# CommsTestBoardV2.net
KiCad netlist of a schematic drawn in EAGLE
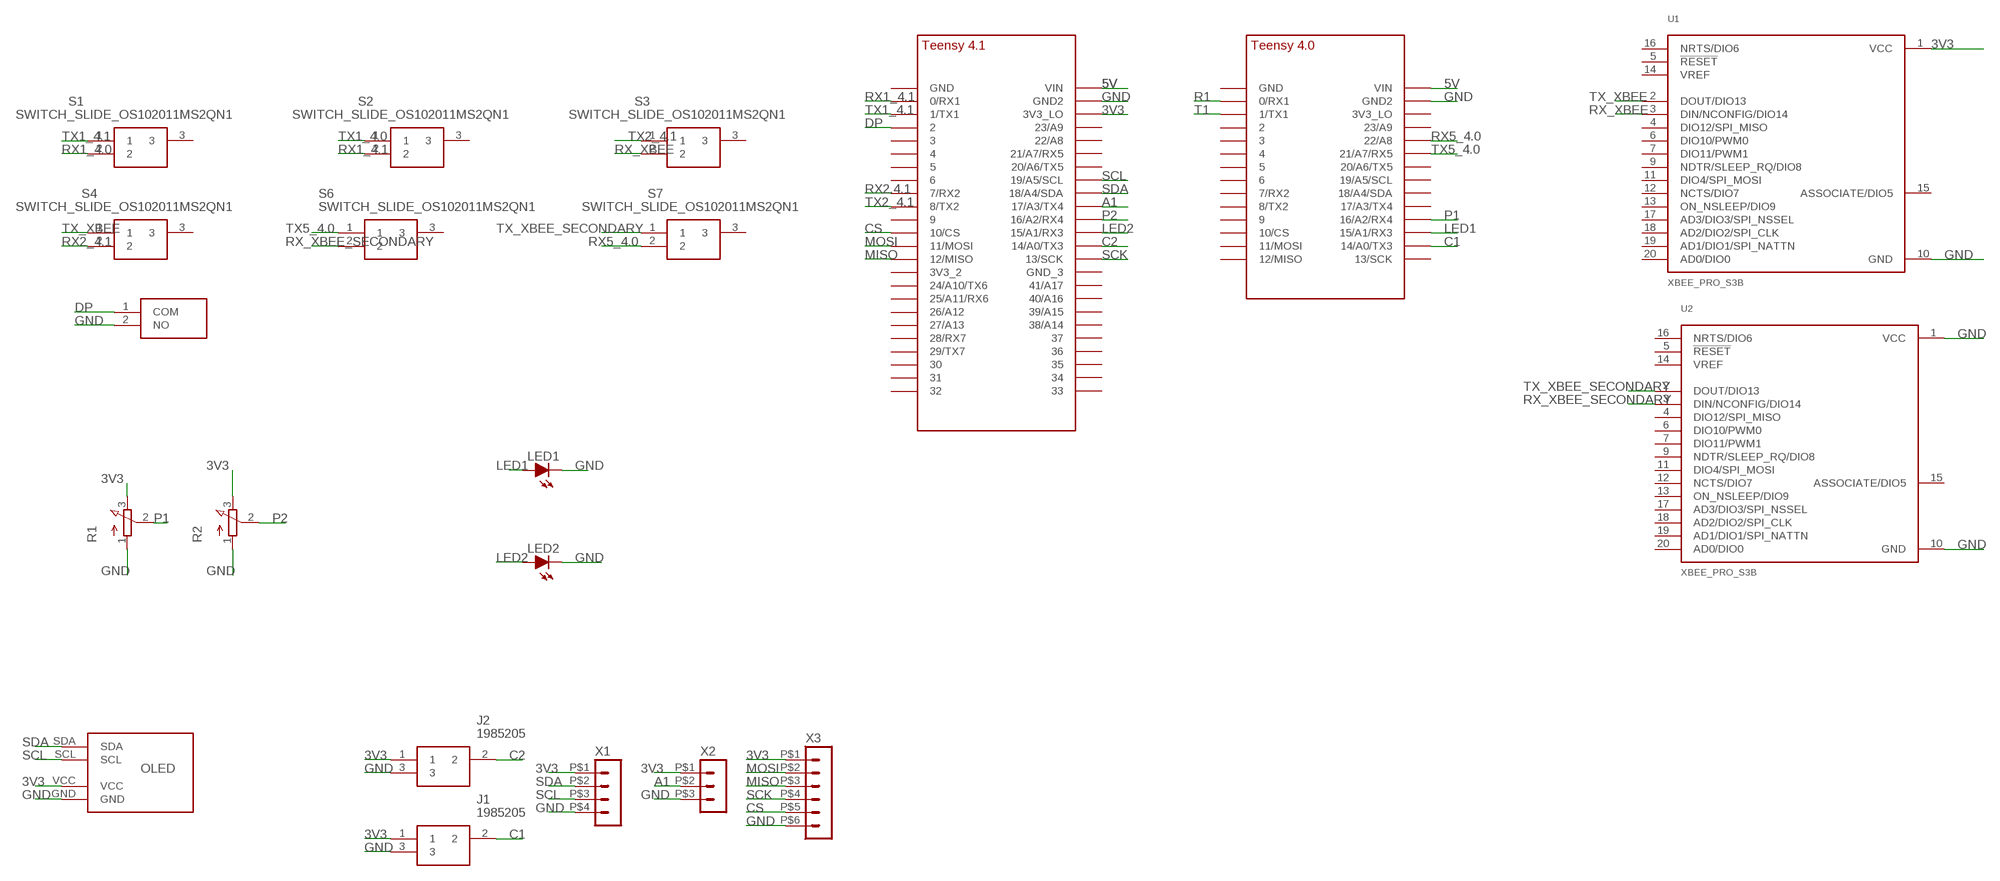
[diagram p0: schematic, sheet 1]

(export (version "E")
  (design (tool "Eeschema 10.0.6"))
  (components
    (comp (ref "J1")
      (value "1985205")
      (footprint "eagle-import:1985205")
      (fields (field (name "MOUSER_PART_NUMBER") "651-1985205"))
      (libsource (lib "eagle-import") (part "1985205"))
    )
    (comp (ref "J2")
      (value "1985205")
      (footprint "eagle-import:1985205")
      (fields (field (name "MOUSER_PART_NUMBER") "651-1985205"))
      (libsource (lib "eagle-import") (part "1985205"))
    )
    (comp (ref "LED1")
      (value "LED-5MM")
      (footprint "eagle-import:LED-5MM")
      (libsource (lib "eagle-import") (part "LED-5MM"))
    )
    (comp (ref "LED2")
      (value "LED-5MM")
      (footprint "eagle-import:LED-5MM")
      (libsource (lib "eagle-import") (part "LED-5MM"))
    )
    (comp (ref "R1")
      (value "POTENTIOMETER")
      (footprint "eagle-import:3RP_1610N")
      (libsource (lib "eagle-import") (part "POTENTIOMETER"))
    )
    (comp (ref "R2")
      (value "POTENTIOMETER")
      (footprint "eagle-import:3RP_1610N")
      (libsource (lib "eagle-import") (part "POTENTIOMETER"))
    )
    (comp (ref "S1")
      (value "SWITCH_SLIDE_OS102011MS2QN1")
      (footprint "eagle-import:OS102011MA1QN1")
      (fields
        (field (name "ARROW_PART_NUMBER") "OS102011MS2QN1")
        (field (name "MOUSER_PART_NUMBER") "611-OS102011MS2QN1")
      )
      (libsource (lib "eagle-import") (part "SWITCH_SLIDE_OS102011MS2QN1"))
    )
    (comp (ref "S2")
      (value "SWITCH_SLIDE_OS102011MS2QN1")
      (footprint "eagle-import:OS102011MA1QN1")
      (fields
        (field (name "ARROW_PART_NUMBER") "OS102011MS2QN1")
        (field (name "MOUSER_PART_NUMBER") "611-OS102011MS2QN1")
      )
      (libsource (lib "eagle-import") (part "SWITCH_SLIDE_OS102011MS2QN1"))
    )
    (comp (ref "S3")
      (value "SWITCH_SLIDE_OS102011MS2QN1")
      (footprint "eagle-import:OS102011MA1QN1")
      (fields
        (field (name "ARROW_PART_NUMBER") "OS102011MS2QN1")
        (field (name "MOUSER_PART_NUMBER") "611-OS102011MS2QN1")
      )
      (libsource (lib "eagle-import") (part "SWITCH_SLIDE_OS102011MS2QN1"))
    )
    (comp (ref "S4")
      (value "SWITCH_SLIDE_OS102011MS2QN1")
      (footprint "eagle-import:OS102011MA1QN1")
      (fields
        (field (name "ARROW_PART_NUMBER") "OS102011MS2QN1")
        (field (name "MOUSER_PART_NUMBER") "611-OS102011MS2QN1")
      )
      (libsource (lib "eagle-import") (part "SWITCH_SLIDE_OS102011MS2QN1"))
    )
    (comp (ref "S5")
      (value "PTS636_SL50_LFS")
      (footprint "eagle-import:PTS636SL50LFS")
      (fields
        (field (name "ARROW_PART_NUMBER") "PTS636 SL50 LFS")
        (field (name "MOUSER_PART_NUMBER") "611-PTS636SL50LFS")
      )
      (libsource (lib "eagle-import") (part "PTS636_SL50_LFS"))
    )
    (comp (ref "S6")
      (value "SWITCH_SLIDE_OS102011MS2QN1")
      (footprint "eagle-import:OS102011MA1QN1")
      (fields
        (field (name "ARROW_PART_NUMBER") "OS102011MS2QN1")
        (field (name "MOUSER_PART_NUMBER") "611-OS102011MS2QN1")
      )
      (libsource (lib "eagle-import") (part "SWITCH_SLIDE_OS102011MS2QN1"))
    )
    (comp (ref "S7")
      (value "SWITCH_SLIDE_OS102011MS2QN1")
      (footprint "eagle-import:OS102011MA1QN1")
      (fields
        (field (name "ARROW_PART_NUMBER") "OS102011MS2QN1")
        (field (name "MOUSER_PART_NUMBER") "611-OS102011MS2QN1")
      )
      (libsource (lib "eagle-import") (part "SWITCH_SLIDE_OS102011MS2QN1"))
    )
    (comp (ref "U$1")
      (value "TEENSY_4.0_SIMPLE")
      (footprint "eagle-import:TEENSY_4.0_SIMPLE")
      (libsource (lib "eagle-import") (part "TEENSY_4.0_SIMPLE"))
    )
    (comp (ref "U$3")
      (value "TEENSY_4.1_SIMPLE")
      (footprint "eagle-import:TEENSY_4.1_SIMPLE")
      (libsource (lib "eagle-import") (part "TEENSY_4.1_SIMPLE"))
    )
    (comp (ref "U$4")
      (value "OLED_SSD1306")
      (footprint "eagle-import:OLED_SSD1306")
      (libsource (lib "eagle-import") (part "OLED_SSD1306"))
    )
    (comp (ref "U1")
      (value "XBEE_PRO_S3B")
      (footprint "eagle-import:XBEE_PRO_S3B")
      (fields
        (field (name "DIGI-KEY_PART_NUMBER") "602-1293-ND")
        (field (name "MF") "Digi International")
        (field (name "MP") "XBP9B-XCST-001")
      )
      (libsource (lib "eagle-import") (part "XBEE_PRO_S3B"))
    )
    (comp (ref "U2")
      (value "XBEE_PRO_S3B")
      (footprint "eagle-import:XBEE_PRO_S3B")
      (fields
        (field (name "DIGI-KEY_PART_NUMBER") "602-1293-ND")
        (field (name "MF") "Digi International")
        (field (name "MP") "XBP9B-XCST-001")
      )
      (libsource (lib "eagle-import") (part "XBEE_PRO_S3B"))
    )
    (comp (ref "X1")
      (value "HEADER_POS4_43045-0401")
      (footprint "eagle-import:43045-0400")
      (libsource (lib "eagle-import") (part "HEADER_POS4_?43045-0401"))
    )
    (comp (ref "X2")
      (value "HEADER_POS3_43650-0300")
      (footprint "eagle-import:43650-0300")
      (libsource (lib "eagle-import") (part "HEADER_POS3_?43650-0300"))
    )
    (comp (ref "X3")
      (value "HEADER_POS6_43045-0600")
      (footprint "eagle-import:43045-0600")
      (libsource (lib "eagle-import") (part "HEADER_POS6_?43045-0600"))
    )
  )
  (nets
    (net (code "1") (name "/3V3") (class "Default")
      (node (ref "J1") (pin "1") (pinfunction "1_1") (pintype "bidirectional"))
      (node (ref "J2") (pin "1") (pinfunction "1_1") (pintype "bidirectional"))
      (node (ref "R1") (pin "3") (pinfunction "E_3") (pintype "passive"))
      (node (ref "R2") (pin "3") (pinfunction "E_3") (pintype "passive"))
      (node (ref "U$3") (pin "3V3_LO") (pinfunction "3V3_LO_3V3_LO") (pintype "bidirectional"))
      (node (ref "U$4") (pin "VCC") (pinfunction "VCC_VCC") (pintype "bidirectional"))
      (node (ref "U1") (pin "1") (pinfunction "VCC_1") (pintype "power_in"))
      (node (ref "X1") (pin "P$1") (pinfunction "1_P$1") (pintype "passive"))
      (node (ref "X2") (pin "P$1") (pinfunction "1_P$1") (pintype "passive"))
      (node (ref "X3") (pin "P$1") (pinfunction "1_P$1") (pintype "passive"))
    )
    (net (code "2") (name "/5V") (class "Default")
      (node (ref "U$1") (pin "VIN") (pinfunction "VIN_VIN") (pintype "bidirectional"))
      (node (ref "U$3") (pin "VIN") (pinfunction "VIN_VIN") (pintype "bidirectional"))
    )
    (net (code "3") (name "/A1") (class "Default")
      (node (ref "U$3") (pin "17/A3") (pinfunction "17/A3/TX4_17/A3") (pintype "bidirectional"))
      (node (ref "X2") (pin "P$2") (pinfunction "2_P$2") (pintype "passive"))
    )
    (net (code "4") (name "/C1") (class "Default")
      (node (ref "J1") (pin "2") (pinfunction "2_2") (pintype "bidirectional"))
      (node (ref "U$1") (pin "14/A0") (pinfunction "14/A0/TX3_14/A0") (pintype "bidirectional"))
    )
    (net (code "5") (name "/C2") (class "Default")
      (node (ref "J2") (pin "2") (pinfunction "2_2") (pintype "bidirectional"))
      (node (ref "U$3") (pin "14/A0") (pinfunction "14/A0/TX3_14/A0") (pintype "bidirectional"))
    )
    (net (code "6") (name "/CS") (class "Default")
      (node (ref "U$3") (pin "10/CS") (pinfunction "10/CS_10/CS") (pintype "bidirectional"))
      (node (ref "X3") (pin "P$5") (pinfunction "5_P$5") (pintype "passive"))
    )
    (net (code "7") (name "/DP") (class "Default")
      (node (ref "S5") (pin "1") (pinfunction "COM_1") (pintype "bidirectional"))
      (node (ref "U$3") (pin "2") (pinfunction "2_2") (pintype "bidirectional"))
    )
    (net (code "8") (name "/GND") (class "Default")
      (node (ref "J1") (pin "3") (pinfunction "3_3") (pintype "bidirectional"))
      (node (ref "J2") (pin "3") (pinfunction "3_3") (pintype "bidirectional"))
      (node (ref "LED1") (pin "K") (pinfunction "C_K") (pintype "passive"))
      (node (ref "LED2") (pin "K") (pinfunction "C_K") (pintype "passive"))
      (node (ref "R1") (pin "1") (pinfunction "A_1") (pintype "passive"))
      (node (ref "R2") (pin "1") (pinfunction "A_1") (pintype "passive"))
      (node (ref "S5") (pin "2") (pinfunction "NO_2") (pintype "bidirectional"))
      (node (ref "U$1") (pin "GND2") (pinfunction "GND2_GND2") (pintype "bidirectional"))
      (node (ref "U$3") (pin "GND2") (pinfunction "GND2_GND2") (pintype "bidirectional"))
      (node (ref "U$4") (pin "GND") (pinfunction "GND_GND") (pintype "bidirectional"))
      (node (ref "U1") (pin "10") (pinfunction "GND_10") (pintype "power_in"))
      (node (ref "U2") (pin "1") (pinfunction "VCC_1") (pintype "power_in"))
      (node (ref "U2") (pin "10") (pinfunction "GND_10") (pintype "power_in"))
      (node (ref "X1") (pin "P$4") (pinfunction "4_P$4") (pintype "passive"))
      (node (ref "X2") (pin "P$3") (pinfunction "3_P$3") (pintype "passive"))
      (node (ref "X3") (pin "P$6") (pinfunction "6_P$6") (pintype "passive"))
    )
    (net (code "9") (name "/LED1") (class "Default")
      (node (ref "LED1") (pin "A") (pinfunction "A_A") (pintype "passive"))
      (node (ref "U$1") (pin "15/A1") (pinfunction "15/A1/RX3_15/A1") (pintype "bidirectional"))
    )
    (net (code "10") (name "/LED2") (class "Default")
      (node (ref "LED2") (pin "A") (pinfunction "A_A") (pintype "passive"))
      (node (ref "U$3") (pin "15/A1") (pinfunction "15/A1/RX3_15/A1") (pintype "bidirectional"))
    )
    (net (code "11") (name "/MISO") (class "Default")
      (node (ref "U$3") (pin "12/MISO") (pinfunction "12/MISO_12/MISO") (pintype "bidirectional"))
      (node (ref "X3") (pin "P$3") (pinfunction "3_P$3") (pintype "passive"))
    )
    (net (code "12") (name "/MOSI") (class "Default")
      (node (ref "U$3") (pin "11/MOSI") (pinfunction "11/MOSI_11/MOSI") (pintype "bidirectional"))
      (node (ref "X3") (pin "P$2") (pinfunction "2_P$2") (pintype "passive"))
    )
    (net (code "13") (name "/P1") (class "Default")
      (node (ref "R1") (pin "2") (pinfunction "S_2") (pintype "passive"))
      (node (ref "U$1") (pin "16/A2") (pinfunction "16/A2/RX4_16/A2") (pintype "bidirectional"))
    )
    (net (code "14") (name "/P2") (class "Default")
      (node (ref "R2") (pin "2") (pinfunction "S_2") (pintype "passive"))
      (node (ref "U$3") (pin "16/A2") (pinfunction "16/A2/RX4_16/A2") (pintype "bidirectional"))
    )
    (net (code "15") (name "/R1") (class "Default")
      (node (ref "U$1") (pin "0/RX") (pinfunction "0/RX1_0/RX") (pintype "bidirectional"))
    )
    (net (code "16") (name "/RX1_4.0") (class "Default")
      (node (ref "S1") (pin "2") (pinfunction "2_2") (pintype "bidirectional"))
    )
    (net (code "17") (name "/RX1_4.1") (class "Default")
      (node (ref "S2") (pin "2") (pinfunction "2_2") (pintype "bidirectional"))
      (node (ref "U$3") (pin "0/RX") (pinfunction "0/RX1_0/RX") (pintype "bidirectional"))
    )
    (net (code "18") (name "/RX2.4.1") (class "Default")
      (node (ref "U$3") (pin "7") (pinfunction "7/RX2_7") (pintype "bidirectional"))
    )
    (net (code "19") (name "/RX2_4.1") (class "Default")
      (node (ref "S4") (pin "2") (pinfunction "2_2") (pintype "bidirectional"))
    )
    (net (code "20") (name "/RX5_4.0") (class "Default")
      (node (ref "S7") (pin "2") (pinfunction "2_2") (pintype "bidirectional"))
      (node (ref "U$1") (pin "22/A8") (pinfunction "22/A8_22/A8") (pintype "bidirectional"))
    )
    (net (code "21") (name "/RX_XBEE") (class "Default")
      (node (ref "S3") (pin "2") (pinfunction "2_2") (pintype "bidirectional"))
      (node (ref "U1") (pin "3") (pinfunction "DIN/NCONFIG/DIO14_3") (pintype "bidirectional"))
    )
    (net (code "22") (name "/RX_XBEE_SECONDARY") (class "Default")
      (node (ref "S6") (pin "2") (pinfunction "2_2") (pintype "bidirectional"))
      (node (ref "U2") (pin "3") (pinfunction "DIN/NCONFIG/DIO14_3") (pintype "bidirectional"))
    )
    (net (code "23") (name "/SCK") (class "Default")
      (node (ref "U$3") (pin "13/SCK") (pinfunction "13/SCK_13/SCK") (pintype "bidirectional"))
      (node (ref "X3") (pin "P$4") (pinfunction "4_P$4") (pintype "passive"))
    )
    (net (code "24") (name "/SCL") (class "Default")
      (node (ref "U$3") (pin "19/A5/SCL") (pinfunction "19/A5/SCL_19/A5/SCL") (pintype "bidirectional"))
      (node (ref "U$4") (pin "SCL") (pinfunction "SCL_SCL") (pintype "bidirectional"))
      (node (ref "X1") (pin "P$3") (pinfunction "3_P$3") (pintype "passive"))
    )
    (net (code "25") (name "/SDA") (class "Default")
      (node (ref "U$3") (pin "18/A4/SDA") (pinfunction "18/A4/SDA_18/A4/SDA") (pintype "bidirectional"))
      (node (ref "U$4") (pin "SDA") (pinfunction "SDA_SDA") (pintype "bidirectional"))
      (node (ref "X1") (pin "P$2") (pinfunction "2_P$2") (pintype "passive"))
    )
    (net (code "26") (name "/T1") (class "Default")
      (node (ref "U$1") (pin "1/TX") (pinfunction "1/TX1_1/TX") (pintype "bidirectional"))
    )
    (net (code "27") (name "/TX1_4.0") (class "Default")
      (node (ref "S2") (pin "1") (pinfunction "1_1") (pintype "bidirectional"))
    )
    (net (code "28") (name "/TX1_4.1") (class "Default")
      (node (ref "S1") (pin "1") (pinfunction "1_1") (pintype "bidirectional"))
      (node (ref "U$3") (pin "1/TX") (pinfunction "1/TX1_1/TX") (pintype "bidirectional"))
    )
    (net (code "29") (name "/TX2_4.1") (class "Default")
      (node (ref "S3") (pin "1") (pinfunction "1_1") (pintype "bidirectional"))
      (node (ref "U$3") (pin "8") (pinfunction "8/TX2_8") (pintype "bidirectional"))
    )
    (net (code "30") (name "/TX5_4.0") (class "Default")
      (node (ref "S6") (pin "1") (pinfunction "1_1") (pintype "bidirectional"))
      (node (ref "U$1") (pin "21/A7") (pinfunction "21/A7/RX5_21/A7") (pintype "bidirectional"))
    )
    (net (code "31") (name "/TX_XBEE") (class "Default")
      (node (ref "S4") (pin "1") (pinfunction "1_1") (pintype "bidirectional"))
      (node (ref "U1") (pin "2") (pinfunction "DOUT/DIO13_2") (pintype "bidirectional"))
    )
    (net (code "32") (name "/TX_XBEE_SECONDARY") (class "Default")
      (node (ref "S7") (pin "1") (pinfunction "1_1") (pintype "bidirectional"))
      (node (ref "U2") (pin "2") (pinfunction "DOUT/DIO13_2") (pintype "bidirectional"))
    )
    (net (code "33") (name "unconnected-(S1-Pad3)") (class "Default")
      (node (ref "S1") (pin "3") (pinfunction "3_3") (pintype "bidirectional"))
    )
    (net (code "34") (name "unconnected-(S2-Pad3)") (class "Default")
      (node (ref "S2") (pin "3") (pinfunction "3_3") (pintype "bidirectional"))
    )
    (net (code "35") (name "unconnected-(S3-Pad3)") (class "Default")
      (node (ref "S3") (pin "3") (pinfunction "3_3") (pintype "bidirectional"))
    )
    (net (code "36") (name "unconnected-(S4-Pad3)") (class "Default")
      (node (ref "S4") (pin "3") (pinfunction "3_3") (pintype "bidirectional"))
    )
    (net (code "37") (name "unconnected-(S6-Pad3)") (class "Default")
      (node (ref "S6") (pin "3") (pinfunction "3_3") (pintype "bidirectional"))
    )
    (net (code "38") (name "unconnected-(S7-Pad3)") (class "Default")
      (node (ref "S7") (pin "3") (pinfunction "3_3") (pintype "bidirectional"))
    )
    (net (code "39") (name "unconnected-(U$1-3-Pad3{slash}CANTX)") (class "Default")
      (node (ref "U$1") (pin "3/CANTX") (pinfunction "3_3/CANTX") (pintype "bidirectional"))
    )
    (net (code "40") (name "unconnected-(U$1-4-Pad4{slash}CANRX)") (class "Default")
      (node (ref "U$1") (pin "4/CANRX") (pinfunction "4_4/CANRX") (pintype "bidirectional"))
    )
    (net (code "41") (name "unconnected-(U$1-7{slash}RX2-Pad7)") (class "Default")
      (node (ref "U$1") (pin "7") (pinfunction "7/RX2_7") (pintype "bidirectional"))
    )
    (net (code "42") (name "unconnected-(U$1-8{slash}TX2-Pad8)") (class "Default")
      (node (ref "U$1") (pin "8") (pinfunction "8/TX2_8") (pintype "bidirectional"))
    )
    (net (code "43") (name "unconnected-(U$1-9-Pad9{slash}CS)") (class "Default")
      (node (ref "U$1") (pin "9/CS") (pinfunction "9_9/CS") (pintype "bidirectional"))
    )
    (net (code "44") (name "unconnected-(U$1-17{slash}A3{slash}TX4-Pad17{slash}A3)") (class "Default")
      (node (ref "U$1") (pin "17/A3") (pinfunction "17/A3/TX4_17/A3") (pintype "bidirectional"))
    )
    (net (code "45") (name "unconnected-(U$1-20{slash}A6{slash}TX5-Pad20{slash}A6)") (class "Default")
      (node (ref "U$1") (pin "20/A6") (pinfunction "20/A6/TX5_20/A6") (pintype "bidirectional"))
    )
    (net (code "46") (name "unconnected-(U$1-Pad2)") (class "Default")
      (node (ref "U$1") (pin "2") (pinfunction "2_2") (pintype "bidirectional"))
    )
    (net (code "47") (name "unconnected-(U$1-Pad3V3_LO)") (class "Default")
      (node (ref "U$1") (pin "3V3_LO") (pinfunction "3V3_LO_3V3_LO") (pintype "bidirectional"))
    )
    (net (code "48") (name "unconnected-(U$1-Pad5)") (class "Default")
      (node (ref "U$1") (pin "5") (pinfunction "5_5") (pintype "bidirectional"))
    )
    (net (code "49") (name "unconnected-(U$1-Pad6)") (class "Default")
      (node (ref "U$1") (pin "6") (pinfunction "6_6") (pintype "bidirectional"))
    )
    (net (code "50") (name "unconnected-(U$1-Pad10{slash}CS)") (class "Default")
      (node (ref "U$1") (pin "10/CS") (pinfunction "10/CS_10/CS") (pintype "bidirectional"))
    )
    (net (code "51") (name "unconnected-(U$1-Pad11{slash}MOSI)") (class "Default")
      (node (ref "U$1") (pin "11/MOSI") (pinfunction "11/MOSI_11/MOSI") (pintype "bidirectional"))
    )
    (net (code "52") (name "unconnected-(U$1-Pad12{slash}MISO)") (class "Default")
      (node (ref "U$1") (pin "12/MISO") (pinfunction "12/MISO_12/MISO") (pintype "bidirectional"))
    )
    (net (code "53") (name "unconnected-(U$1-Pad13{slash}SCK)") (class "Default")
      (node (ref "U$1") (pin "13/SCK") (pinfunction "13/SCK_13/SCK") (pintype "bidirectional"))
    )
    (net (code "54") (name "unconnected-(U$1-Pad18{slash}A4{slash}SDA)") (class "Default")
      (node (ref "U$1") (pin "18/A4/SDA") (pinfunction "18/A4/SDA_18/A4/SDA") (pintype "bidirectional"))
    )
    (net (code "55") (name "unconnected-(U$1-Pad19{slash}A5{slash}SCL)") (class "Default")
      (node (ref "U$1") (pin "19/A5/SCL") (pinfunction "19/A5/SCL_19/A5/SCL") (pintype "bidirectional"))
    )
    (net (code "56") (name "unconnected-(U$1-Pad23{slash}A9)") (class "Default")
      (node (ref "U$1") (pin "23/A9") (pinfunction "23/A9_23/A9") (pintype "bidirectional"))
    )
    (net (code "57") (name "unconnected-(U$1-PadGND)") (class "Default")
      (node (ref "U$1") (pin "GND") (pinfunction "GND_GND") (pintype "bidirectional"))
    )
    (net (code "58") (name "unconnected-(U$3-3-Pad3{slash}CANTX)") (class "Default")
      (node (ref "U$3") (pin "3/CANTX") (pinfunction "3_3/CANTX") (pintype "bidirectional"))
    )
    (net (code "59") (name "unconnected-(U$3-4-Pad4{slash}CANRX)") (class "Default")
      (node (ref "U$3") (pin "4/CANRX") (pinfunction "4_4/CANRX") (pintype "bidirectional"))
    )
    (net (code "60") (name "unconnected-(U$3-9-Pad9{slash}CS)") (class "Default")
      (node (ref "U$3") (pin "9/CS") (pinfunction "9_9/CS") (pintype "bidirectional"))
    )
    (net (code "61") (name "unconnected-(U$3-20{slash}A6{slash}TX5-Pad20{slash}A6)") (class "Default")
      (node (ref "U$3") (pin "20/A6") (pinfunction "20/A6/TX5_20/A6") (pintype "bidirectional"))
    )
    (net (code "62") (name "unconnected-(U$3-21{slash}A7{slash}RX5-Pad21{slash}A7)") (class "Default")
      (node (ref "U$3") (pin "21/A7") (pinfunction "21/A7/RX5_21/A7") (pintype "bidirectional"))
    )
    (net (code "63") (name "unconnected-(U$3-24{slash}A10{slash}TX6-Pad24{slash}A10)") (class "Default")
      (node (ref "U$3") (pin "24/A10") (pinfunction "24/A10/TX6_24/A10") (pintype "bidirectional"))
    )
    (net (code "64") (name "unconnected-(U$3-25{slash}A11{slash}RX6-Pad25{slash}A11)") (class "Default")
      (node (ref "U$3") (pin "25/A11") (pinfunction "25/A11/RX6_25/A11") (pintype "bidirectional"))
    )
    (net (code "65") (name "unconnected-(U$3-28{slash}RX7-Pad28)") (class "Default")
      (node (ref "U$3") (pin "28") (pinfunction "28/RX7_28") (pintype "bidirectional"))
    )
    (net (code "66") (name "unconnected-(U$3-29{slash}TX7-Pad29)") (class "Default")
      (node (ref "U$3") (pin "29") (pinfunction "29/TX7_29") (pintype "bidirectional"))
    )
    (net (code "67") (name "unconnected-(U$3-GND_3-PadGND3)") (class "Default")
      (node (ref "U$3") (pin "GND3") (pinfunction "GND_3_GND3") (pintype "bidirectional"))
    )
    (net (code "68") (name "unconnected-(U$3-Pad3V3_2)") (class "Default")
      (node (ref "U$3") (pin "3V3_2") (pinfunction "3V3_2_3V3_2") (pintype "bidirectional"))
    )
    (net (code "69") (name "unconnected-(U$3-Pad5)") (class "Default")
      (node (ref "U$3") (pin "5") (pinfunction "5_5") (pintype "bidirectional"))
    )
    (net (code "70") (name "unconnected-(U$3-Pad6)") (class "Default")
      (node (ref "U$3") (pin "6") (pinfunction "6_6") (pintype "bidirectional"))
    )
    (net (code "71") (name "unconnected-(U$3-Pad22{slash}A8)") (class "Default")
      (node (ref "U$3") (pin "22/A8") (pinfunction "22/A8_22/A8") (pintype "bidirectional"))
    )
    (net (code "72") (name "unconnected-(U$3-Pad23{slash}A9)") (class "Default")
      (node (ref "U$3") (pin "23/A9") (pinfunction "23/A9_23/A9") (pintype "bidirectional"))
    )
    (net (code "73") (name "unconnected-(U$3-Pad26{slash}A12)") (class "Default")
      (node (ref "U$3") (pin "26/A12") (pinfunction "26/A12_26/A12") (pintype "bidirectional"))
    )
    (net (code "74") (name "unconnected-(U$3-Pad27{slash}A13)") (class "Default")
      (node (ref "U$3") (pin "27/A13") (pinfunction "27/A13_27/A13") (pintype "bidirectional"))
    )
    (net (code "75") (name "unconnected-(U$3-Pad30)") (class "Default")
      (node (ref "U$3") (pin "30") (pinfunction "30_30") (pintype "bidirectional"))
    )
    (net (code "76") (name "unconnected-(U$3-Pad31)") (class "Default")
      (node (ref "U$3") (pin "31") (pinfunction "31_31") (pintype "bidirectional"))
    )
    (net (code "77") (name "unconnected-(U$3-Pad32)") (class "Default")
      (node (ref "U$3") (pin "32") (pinfunction "32_32") (pintype "bidirectional"))
    )
    (net (code "78") (name "unconnected-(U$3-Pad33)") (class "Default")
      (node (ref "U$3") (pin "33") (pinfunction "33_33") (pintype "bidirectional"))
    )
    (net (code "79") (name "unconnected-(U$3-Pad34)") (class "Default")
      (node (ref "U$3") (pin "34") (pinfunction "34_34") (pintype "bidirectional"))
    )
    (net (code "80") (name "unconnected-(U$3-Pad35)") (class "Default")
      (node (ref "U$3") (pin "35") (pinfunction "35_35") (pintype "bidirectional"))
    )
    (net (code "81") (name "unconnected-(U$3-Pad36)") (class "Default")
      (node (ref "U$3") (pin "36") (pinfunction "36_36") (pintype "bidirectional"))
    )
    (net (code "82") (name "unconnected-(U$3-Pad37)") (class "Default")
      (node (ref "U$3") (pin "37") (pinfunction "37_37") (pintype "bidirectional"))
    )
    (net (code "83") (name "unconnected-(U$3-Pad38{slash}A14)") (class "Default")
      (node (ref "U$3") (pin "38/A14") (pinfunction "38/A14_38/A14") (pintype "bidirectional"))
    )
    (net (code "84") (name "unconnected-(U$3-Pad39{slash}A15)") (class "Default")
      (node (ref "U$3") (pin "39/A15") (pinfunction "39/A15_39/A15") (pintype "bidirectional"))
    )
    (net (code "85") (name "unconnected-(U$3-Pad40{slash}A16)") (class "Default")
      (node (ref "U$3") (pin "40/A16") (pinfunction "40/A16_40/A16") (pintype "bidirectional"))
    )
    (net (code "86") (name "unconnected-(U$3-Pad41{slash}A17)") (class "Default")
      (node (ref "U$3") (pin "41/A17") (pinfunction "41/A17_41/A17") (pintype "bidirectional"))
    )
    (net (code "87") (name "unconnected-(U$3-PadGND)") (class "Default")
      (node (ref "U$3") (pin "GND") (pinfunction "GND_GND") (pintype "bidirectional"))
    )
    (net (code "88") (name "unconnected-(U1-AD0{slash}DIO0-Pad20)") (class "Default")
      (node (ref "U1") (pin "20") (pinfunction "AD0/DIO0_20") (pintype "bidirectional"))
    )
    (net (code "89") (name "unconnected-(U1-AD1{slash}DIO1{slash}SPI_NATTN-Pad19)") (class "Default")
      (node (ref "U1") (pin "19") (pinfunction "AD1/DIO1/SPI_NATTN_19") (pintype "bidirectional"))
    )
    (net (code "90") (name "unconnected-(U1-AD2{slash}DIO2{slash}SPI_CLK-Pad18)") (class "Default")
      (node (ref "U1") (pin "18") (pinfunction "AD2/DIO2/SPI_CLK_18") (pintype "bidirectional"))
    )
    (net (code "91") (name "unconnected-(U1-AD3{slash}DIO3{slash}SPI_NSSEL-Pad17)") (class "Default")
      (node (ref "U1") (pin "17") (pinfunction "AD3/DIO3/SPI_NSSEL_17") (pintype "bidirectional"))
    )
    (net (code "92") (name "unconnected-(U1-ASSOCIATE{slash}DIO5-Pad15)") (class "Default")
      (node (ref "U1") (pin "15") (pinfunction "ASSOCIATE/DIO5_15") (pintype "output"))
    )
    (net (code "93") (name "unconnected-(U1-DIO4{slash}SPI_MOSI-Pad11)") (class "Default")
      (node (ref "U1") (pin "11") (pinfunction "DIO4/SPI_MOSI_11") (pintype "bidirectional"))
    )
    (net (code "94") (name "unconnected-(U1-DIO10{slash}PWM0-Pad6)") (class "Default")
      (node (ref "U1") (pin "6") (pinfunction "DIO10/PWM0_6") (pintype "bidirectional"))
    )
    (net (code "95") (name "unconnected-(U1-DIO11{slash}PWM1-Pad7)") (class "Default")
      (node (ref "U1") (pin "7") (pinfunction "DIO11/PWM1_7") (pintype "bidirectional"))
    )
    (net (code "96") (name "unconnected-(U1-DIO12{slash}SPI_MISO-Pad4)") (class "Default")
      (node (ref "U1") (pin "4") (pinfunction "DIO12/SPI_MISO_4") (pintype "bidirectional"))
    )
    (net (code "97") (name "unconnected-(U1-NCTS{slash}DIO7-Pad12)") (class "Default")
      (node (ref "U1") (pin "12") (pinfunction "NCTS/DIO7_12") (pintype "bidirectional"))
    )
    (net (code "98") (name "unconnected-(U1-NDTR{slash}SLEEP_RQ{slash}DIO8-Pad9)") (class "Default")
      (node (ref "U1") (pin "9") (pinfunction "NDTR/SLEEP_RQ/DIO8_9") (pintype "bidirectional"))
    )
    (net (code "99") (name "unconnected-(U1-NRTS{slash}DIO6-Pad16)") (class "Default")
      (node (ref "U1") (pin "16") (pinfunction "NRTS/DIO6_16") (pintype "input"))
    )
    (net (code "100") (name "unconnected-(U1-ON_NSLEEP{slash}DIO9-Pad13)") (class "Default")
      (node (ref "U1") (pin "13") (pinfunction "ON_NSLEEP/DIO9_13") (pintype "bidirectional"))
    )
    (net (code "101") (name "unconnected-(U1-VREF-Pad14)") (class "Default")
      (node (ref "U1") (pin "14") (pinfunction "VREF_14") (pintype "input"))
    )
    (net (code "102") (name "unconnected-(U1-~{RESET}-Pad5)") (class "Default")
      (node (ref "U1") (pin "5") (pinfunction "~{RESET}_5") (pintype "input"))
    )
    (net (code "103") (name "unconnected-(U2-AD0{slash}DIO0-Pad20)") (class "Default")
      (node (ref "U2") (pin "20") (pinfunction "AD0/DIO0_20") (pintype "bidirectional"))
    )
    (net (code "104") (name "unconnected-(U2-AD1{slash}DIO1{slash}SPI_NATTN-Pad19)") (class "Default")
      (node (ref "U2") (pin "19") (pinfunction "AD1/DIO1/SPI_NATTN_19") (pintype "bidirectional"))
    )
    (net (code "105") (name "unconnected-(U2-AD2{slash}DIO2{slash}SPI_CLK-Pad18)") (class "Default")
      (node (ref "U2") (pin "18") (pinfunction "AD2/DIO2/SPI_CLK_18") (pintype "bidirectional"))
    )
    (net (code "106") (name "unconnected-(U2-AD3{slash}DIO3{slash}SPI_NSSEL-Pad17)") (class "Default")
      (node (ref "U2") (pin "17") (pinfunction "AD3/DIO3/SPI_NSSEL_17") (pintype "bidirectional"))
    )
    (net (code "107") (name "unconnected-(U2-ASSOCIATE{slash}DIO5-Pad15)") (class "Default")
      (node (ref "U2") (pin "15") (pinfunction "ASSOCIATE/DIO5_15") (pintype "output"))
    )
    (net (code "108") (name "unconnected-(U2-DIO4{slash}SPI_MOSI-Pad11)") (class "Default")
      (node (ref "U2") (pin "11") (pinfunction "DIO4/SPI_MOSI_11") (pintype "bidirectional"))
    )
    (net (code "109") (name "unconnected-(U2-DIO10{slash}PWM0-Pad6)") (class "Default")
      (node (ref "U2") (pin "6") (pinfunction "DIO10/PWM0_6") (pintype "bidirectional"))
    )
    (net (code "110") (name "unconnected-(U2-DIO11{slash}PWM1-Pad7)") (class "Default")
      (node (ref "U2") (pin "7") (pinfunction "DIO11/PWM1_7") (pintype "bidirectional"))
    )
    (net (code "111") (name "unconnected-(U2-DIO12{slash}SPI_MISO-Pad4)") (class "Default")
      (node (ref "U2") (pin "4") (pinfunction "DIO12/SPI_MISO_4") (pintype "bidirectional"))
    )
    (net (code "112") (name "unconnected-(U2-NCTS{slash}DIO7-Pad12)") (class "Default")
      (node (ref "U2") (pin "12") (pinfunction "NCTS/DIO7_12") (pintype "bidirectional"))
    )
    (net (code "113") (name "unconnected-(U2-NDTR{slash}SLEEP_RQ{slash}DIO8-Pad9)") (class "Default")
      (node (ref "U2") (pin "9") (pinfunction "NDTR/SLEEP_RQ/DIO8_9") (pintype "bidirectional"))
    )
    (net (code "114") (name "unconnected-(U2-NRTS{slash}DIO6-Pad16)") (class "Default")
      (node (ref "U2") (pin "16") (pinfunction "NRTS/DIO6_16") (pintype "input"))
    )
    (net (code "115") (name "unconnected-(U2-ON_NSLEEP{slash}DIO9-Pad13)") (class "Default")
      (node (ref "U2") (pin "13") (pinfunction "ON_NSLEEP/DIO9_13") (pintype "bidirectional"))
    )
    (net (code "116") (name "unconnected-(U2-VREF-Pad14)") (class "Default")
      (node (ref "U2") (pin "14") (pinfunction "VREF_14") (pintype "input"))
    )
    (net (code "117") (name "unconnected-(U2-~{RESET}-Pad5)") (class "Default")
      (node (ref "U2") (pin "5") (pinfunction "~{RESET}_5") (pintype "input"))
    )
  )
)
